# UsbHub.net
KiCad netlist of a schematic drawn in EasyEDA Pro
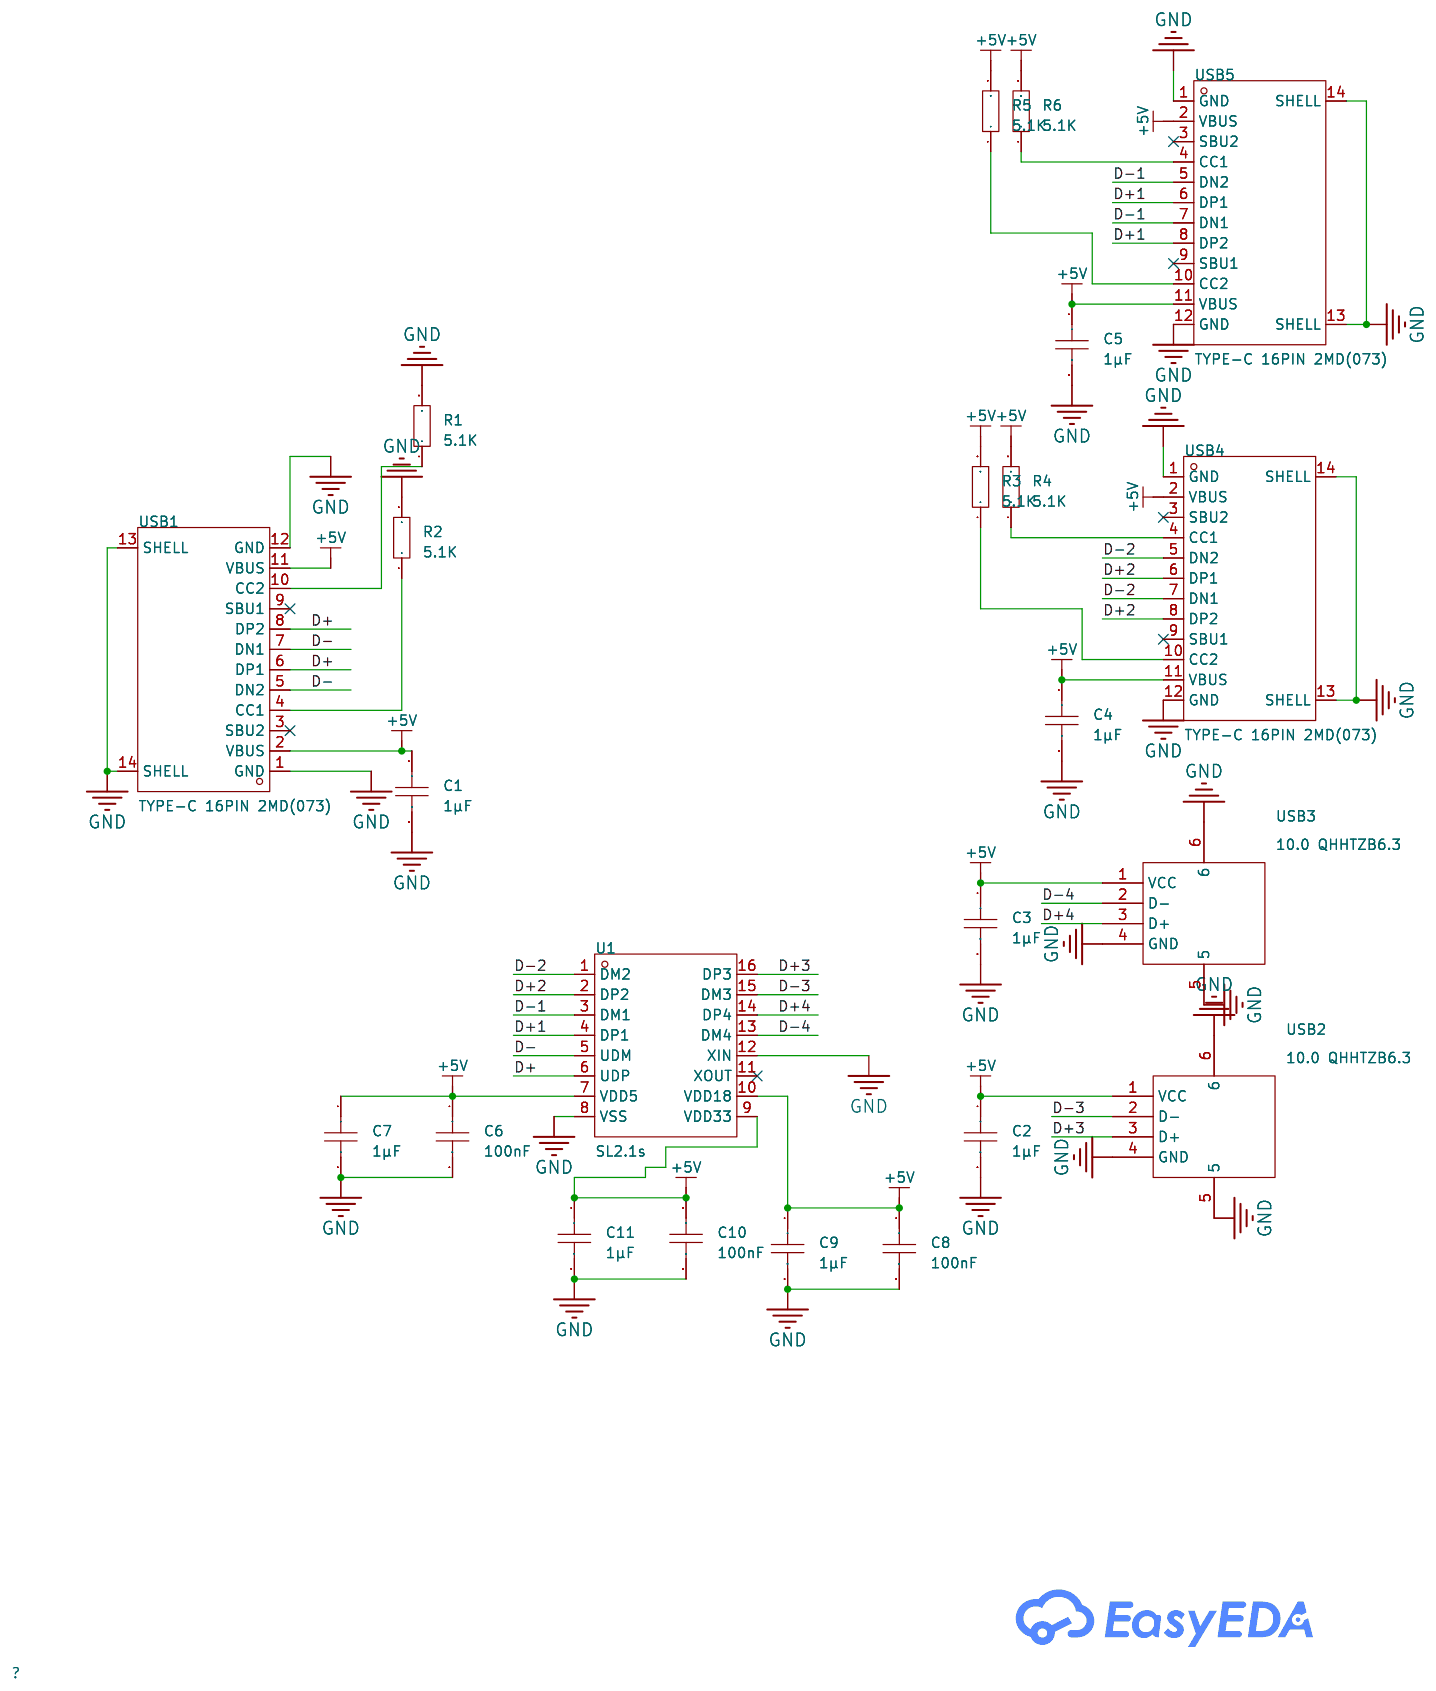
[diagram p0: schematic sheet]

(export (version "E")
  (design (tool "Eeschema 10.0.6"))
  (components
    (comp (ref "C1") (value "1µF") (footprint "easyedapro:C0603") (libsource (lib "easyedapro") (part "CAP")))
    (comp (ref "C2") (value "1µF") (footprint "easyedapro:C0603") (libsource (lib "easyedapro") (part "CAP")))
    (comp (ref "C3") (value "1µF") (footprint "easyedapro:C0603") (libsource (lib "easyedapro") (part "CAP")))
    (comp (ref "C4") (value "1µF") (footprint "easyedapro:C0603") (libsource (lib "easyedapro") (part "CAP")))
    (comp (ref "C5") (value "1µF") (footprint "easyedapro:C0603") (libsource (lib "easyedapro") (part "CAP")))
    (comp (ref "C6")
      (value "100nF")
      (footprint "easyedapro:C0603")
      (libsource (lib "easyedapro") (part "CAP"))
    )
    (comp (ref "C7") (value "1µF") (footprint "easyedapro:C0603") (libsource (lib "easyedapro") (part "CAP")))
    (comp (ref "C8")
      (value "100nF")
      (footprint "easyedapro:C0603")
      (libsource (lib "easyedapro") (part "CAP"))
    )
    (comp (ref "C9") (value "1µF") (footprint "easyedapro:C0603") (libsource (lib "easyedapro") (part "CAP")))
    (comp (ref "C10")
      (value "100nF")
      (footprint "easyedapro:C0603")
      (libsource (lib "easyedapro") (part "CAP"))
    )
    (comp (ref "C11")
      (value "1µF")
      (footprint "easyedapro:C0603")
      (libsource (lib "easyedapro") (part "CAP"))
    )
    (comp (ref "R1")
      (value "5.1K")
      (footprint "easyedapro:R0603")
      (libsource (lib "easyedapro") (part "Res"))
    )
    (comp (ref "R2")
      (value "5.1K")
      (footprint "easyedapro:R0603")
      (libsource (lib "easyedapro") (part "Res"))
    )
    (comp (ref "R3")
      (value "5.1K")
      (footprint "easyedapro:R0603")
      (libsource (lib "easyedapro") (part "Res"))
    )
    (comp (ref "R4")
      (value "5.1K")
      (footprint "easyedapro:R0603")
      (libsource (lib "easyedapro") (part "Res"))
    )
    (comp (ref "R5")
      (value "5.1K")
      (footprint "easyedapro:R0603")
      (libsource (lib "easyedapro") (part "Res"))
    )
    (comp (ref "R6")
      (value "5.1K")
      (footprint "easyedapro:R0603")
      (libsource (lib "easyedapro") (part "Res"))
    )
    (comp (ref "U1")
      (value "SL2.1s")
      (footprint "easyedapro:SSOP-16_L4.6-W2.6-P0.53-LS4.0-BL")
      (fields (field (name "Manufacturer") "CoreChips(和芯润德)"))
      (libsource (lib "easyedapro") (part "SL2.1S"))
    )
    (comp (ref "USB1")
      (value "TYPE-C 16PIN 2MD(073)")
      (footprint "easyedapro:USB-C-SMD_TYPE-C-6PIN-2MD-073")
      (fields (field (name "Manufacturer") "SHOU HAN(首韩)"))
      (libsource (lib "easyedapro") (part "TYPE-C 16PIN 2MD(073)"))
    )
    (comp (ref "USB2")
      (value "10.0 QHHTZB6.3")
      (footprint "easyedapro:USB-A-TH_10.0QHHTZB6.3")
      (fields (field (name "Manufacturer") "SHOU HAN(首韩)"))
      (libsource (lib "easyedapro") (part "10.0 QHHTZB6.3"))
    )
    (comp (ref "USB3")
      (value "10.0 QHHTZB6.3")
      (footprint "easyedapro:USB-A-TH_10.0QHHTZB6.3")
      (fields (field (name "Manufacturer") "SHOU HAN(首韩)"))
      (libsource (lib "easyedapro") (part "10.0 QHHTZB6.3"))
    )
    (comp (ref "USB4")
      (value "TYPE-C 16PIN 2MD(073)")
      (footprint "easyedapro:USB-C-SMD_TYPE-C-6PIN-2MD-073")
      (fields (field (name "Manufacturer") "SHOU HAN(首韩)"))
      (libsource (lib "easyedapro") (part "TYPE-C 16PIN 2MD(073)"))
    )
    (comp (ref "USB5")
      (value "TYPE-C 16PIN 2MD(073)")
      (footprint "easyedapro:USB-C-SMD_TYPE-C-6PIN-2MD-073")
      (fields (field (name "Manufacturer") "SHOU HAN(首韩)"))
      (libsource (lib "easyedapro") (part "TYPE-C 16PIN 2MD(073)"))
    )
  )
  (nets
    (net (code "1") (name "+5V") (class "Default")
      (node (ref "C1") (pin "1") (pinfunction "1_1") (pintype "input"))
      (node (ref "C10") (pin "1") (pinfunction "1_1") (pintype "input"))
      (node (ref "C11") (pin "1") (pinfunction "1_1") (pintype "input"))
      (node (ref "C2") (pin "1") (pinfunction "1_1") (pintype "input"))
      (node (ref "C3") (pin "1") (pinfunction "1_1") (pintype "input"))
      (node (ref "C4") (pin "1") (pinfunction "1_1") (pintype "input"))
      (node (ref "C5") (pin "1") (pinfunction "1_1") (pintype "input"))
      (node (ref "C6") (pin "1") (pinfunction "1_1") (pintype "input"))
      (node (ref "C7") (pin "1") (pinfunction "1_1") (pintype "input"))
      (node (ref "C8") (pin "1") (pinfunction "1_1") (pintype "input"))
      (node (ref "C9") (pin "1") (pinfunction "1_1") (pintype "input"))
      (node (ref "R3") (pin "2") (pinfunction "2_2") (pintype "input"))
      (node (ref "R4") (pin "2") (pinfunction "2_2") (pintype "input"))
      (node (ref "R5") (pin "2") (pinfunction "2_2") (pintype "input"))
      (node (ref "R6") (pin "2") (pinfunction "2_2") (pintype "input"))
      (node (ref "U1") (pin "10") (pinfunction "VDD18_10") (pintype "unspecified"))
      (node (ref "U1") (pin "7") (pinfunction "VDD5_7") (pintype "unspecified"))
      (node (ref "U1") (pin "9") (pinfunction "VDD33_9") (pintype "unspecified"))
      (node (ref "USB1") (pin "11") (pinfunction "VBUS_11") (pintype "unspecified"))
      (node (ref "USB1") (pin "2") (pinfunction "VBUS_2") (pintype "unspecified"))
      (node (ref "USB2") (pin "1") (pinfunction "VCC_1") (pintype "unspecified"))
      (node (ref "USB3") (pin "1") (pinfunction "VCC_1") (pintype "unspecified"))
      (node (ref "USB4") (pin "11") (pinfunction "VBUS_11") (pintype "unspecified"))
      (node (ref "USB4") (pin "2") (pinfunction "VBUS_2") (pintype "unspecified"))
      (node (ref "USB5") (pin "11") (pinfunction "VBUS_11") (pintype "unspecified"))
      (node (ref "USB5") (pin "2") (pinfunction "VBUS_2") (pintype "unspecified"))
    )
    (net (code "2") (name "/D+") (class "Default")
      (node (ref "U1") (pin "6") (pinfunction "UDP_6") (pintype "unspecified"))
      (node (ref "USB1") (pin "6") (pinfunction "DP1_6") (pintype "unspecified"))
      (node (ref "USB1") (pin "8") (pinfunction "DP2_8") (pintype "unspecified"))
    )
    (net (code "3") (name "/D+1") (class "Default")
      (node (ref "U1") (pin "4") (pinfunction "DP1_4") (pintype "unspecified"))
      (node (ref "USB5") (pin "6") (pinfunction "DP1_6") (pintype "unspecified"))
      (node (ref "USB5") (pin "8") (pinfunction "DP2_8") (pintype "unspecified"))
    )
    (net (code "4") (name "/D+2") (class "Default")
      (node (ref "U1") (pin "2") (pinfunction "DP2_2") (pintype "unspecified"))
      (node (ref "USB4") (pin "6") (pinfunction "DP1_6") (pintype "unspecified"))
      (node (ref "USB4") (pin "8") (pinfunction "DP2_8") (pintype "unspecified"))
    )
    (net (code "5") (name "/D+3") (class "Default")
      (node (ref "U1") (pin "16") (pinfunction "DP3_16") (pintype "unspecified"))
      (node (ref "USB2") (pin "3") (pinfunction "D+_3") (pintype "unspecified"))
    )
    (net (code "6") (name "/D+4") (class "Default")
      (node (ref "U1") (pin "14") (pinfunction "DP4_14") (pintype "unspecified"))
      (node (ref "USB3") (pin "3") (pinfunction "D+_3") (pintype "unspecified"))
    )
    (net (code "7") (name "/D-") (class "Default")
      (node (ref "U1") (pin "5") (pinfunction "UDM_5") (pintype "unspecified"))
      (node (ref "USB1") (pin "5") (pinfunction "DN2_5") (pintype "unspecified"))
      (node (ref "USB1") (pin "7") (pinfunction "DN1_7") (pintype "unspecified"))
    )
    (net (code "8") (name "/D-1") (class "Default")
      (node (ref "U1") (pin "3") (pinfunction "DM1_3") (pintype "unspecified"))
      (node (ref "USB5") (pin "5") (pinfunction "DN2_5") (pintype "unspecified"))
      (node (ref "USB5") (pin "7") (pinfunction "DN1_7") (pintype "unspecified"))
    )
    (net (code "9") (name "/D-2") (class "Default")
      (node (ref "U1") (pin "1") (pinfunction "DM2_1") (pintype "unspecified"))
      (node (ref "USB4") (pin "5") (pinfunction "DN2_5") (pintype "unspecified"))
      (node (ref "USB4") (pin "7") (pinfunction "DN1_7") (pintype "unspecified"))
    )
    (net (code "10") (name "/D-3") (class "Default")
      (node (ref "U1") (pin "15") (pinfunction "DM3_15") (pintype "unspecified"))
      (node (ref "USB2") (pin "2") (pinfunction "D-_2") (pintype "unspecified"))
    )
    (net (code "11") (name "/D-4") (class "Default")
      (node (ref "U1") (pin "13") (pinfunction "DM4_13") (pintype "unspecified"))
      (node (ref "USB3") (pin "2") (pinfunction "D-_2") (pintype "unspecified"))
    )
    (net (code "12") (name "GND") (class "Default")
      (node (ref "C1") (pin "2") (pinfunction "2_2") (pintype "input"))
      (node (ref "C10") (pin "2") (pinfunction "2_2") (pintype "input"))
      (node (ref "C11") (pin "2") (pinfunction "2_2") (pintype "input"))
      (node (ref "C2") (pin "2") (pinfunction "2_2") (pintype "input"))
      (node (ref "C3") (pin "2") (pinfunction "2_2") (pintype "input"))
      (node (ref "C4") (pin "2") (pinfunction "2_2") (pintype "input"))
      (node (ref "C5") (pin "2") (pinfunction "2_2") (pintype "input"))
      (node (ref "C6") (pin "2") (pinfunction "2_2") (pintype "input"))
      (node (ref "C7") (pin "2") (pinfunction "2_2") (pintype "input"))
      (node (ref "C8") (pin "2") (pinfunction "2_2") (pintype "input"))
      (node (ref "C9") (pin "2") (pinfunction "2_2") (pintype "input"))
      (node (ref "R1") (pin "2") (pinfunction "2_2") (pintype "input"))
      (node (ref "R2") (pin "2") (pinfunction "2_2") (pintype "input"))
      (node (ref "U1") (pin "12") (pinfunction "XIN_12") (pintype "unspecified"))
      (node (ref "U1") (pin "8") (pinfunction "VSS_8") (pintype "unspecified"))
      (node (ref "USB1") (pin "1") (pinfunction "GND_1") (pintype "unspecified"))
      (node (ref "USB1") (pin "12") (pinfunction "GND_12") (pintype "unspecified"))
      (node (ref "USB1") (pin "13") (pinfunction "SHELL_13") (pintype "unspecified"))
      (node (ref "USB1") (pin "14") (pinfunction "SHELL_14") (pintype "unspecified"))
      (node (ref "USB2") (pin "4") (pinfunction "GND_4") (pintype "unspecified"))
      (node (ref "USB2") (pin "5") (pinfunction "5_5") (pintype "unspecified"))
      (node (ref "USB2") (pin "6") (pinfunction "6_6") (pintype "unspecified"))
      (node (ref "USB3") (pin "4") (pinfunction "GND_4") (pintype "unspecified"))
      (node (ref "USB3") (pin "5") (pinfunction "5_5") (pintype "unspecified"))
      (node (ref "USB3") (pin "6") (pinfunction "6_6") (pintype "unspecified"))
      (node (ref "USB4") (pin "1") (pinfunction "GND_1") (pintype "unspecified"))
      (node (ref "USB4") (pin "12") (pinfunction "GND_12") (pintype "unspecified"))
      (node (ref "USB4") (pin "13") (pinfunction "SHELL_13") (pintype "unspecified"))
      (node (ref "USB4") (pin "14") (pinfunction "SHELL_14") (pintype "unspecified"))
      (node (ref "USB5") (pin "1") (pinfunction "GND_1") (pintype "unspecified"))
      (node (ref "USB5") (pin "12") (pinfunction "GND_12") (pintype "unspecified"))
      (node (ref "USB5") (pin "13") (pinfunction "SHELL_13") (pintype "unspecified"))
      (node (ref "USB5") (pin "14") (pinfunction "SHELL_14") (pintype "unspecified"))
    )
    (net (code "13") (name "Net-(USB1-CC1)") (class "Default")
      (node (ref "R2") (pin "1") (pinfunction "1_1") (pintype "input"))
      (node (ref "USB1") (pin "4") (pinfunction "CC1_4") (pintype "unspecified"))
    )
    (net (code "14") (name "Net-(USB1-CC2)") (class "Default")
      (node (ref "R1") (pin "1") (pinfunction "1_1") (pintype "input"))
      (node (ref "USB1") (pin "10") (pinfunction "CC2_10") (pintype "unspecified"))
    )
    (net (code "15") (name "Net-(USB4-CC1)") (class "Default")
      (node (ref "R4") (pin "1") (pinfunction "1_1") (pintype "input"))
      (node (ref "USB4") (pin "4") (pinfunction "CC1_4") (pintype "unspecified"))
    )
    (net (code "16") (name "Net-(USB4-CC2)") (class "Default")
      (node (ref "R3") (pin "1") (pinfunction "1_1") (pintype "input"))
      (node (ref "USB4") (pin "10") (pinfunction "CC2_10") (pintype "unspecified"))
    )
    (net (code "17") (name "Net-(USB5-CC1)") (class "Default")
      (node (ref "R6") (pin "1") (pinfunction "1_1") (pintype "input"))
      (node (ref "USB5") (pin "4") (pinfunction "CC1_4") (pintype "unspecified"))
    )
    (net (code "18") (name "Net-(USB5-CC2)") (class "Default")
      (node (ref "R5") (pin "1") (pinfunction "1_1") (pintype "input"))
      (node (ref "USB5") (pin "10") (pinfunction "CC2_10") (pintype "unspecified"))
    )
    (net (code "19") (name "unconnected-(U1-XOUT-Pad11)") (class "Default")
      (node (ref "U1") (pin "11") (pinfunction "XOUT_11") (pintype "unspecified+no_connect"))
    )
    (net (code "20") (name "unconnected-(USB1-SBU1-Pad9)") (class "Default")
      (node (ref "USB1") (pin "9") (pinfunction "SBU1_9") (pintype "unspecified+no_connect"))
    )
    (net (code "21") (name "unconnected-(USB1-SBU2-Pad3)") (class "Default")
      (node (ref "USB1") (pin "3") (pinfunction "SBU2_3") (pintype "unspecified+no_connect"))
    )
    (net (code "22") (name "unconnected-(USB4-SBU1-Pad9)") (class "Default")
      (node (ref "USB4") (pin "9") (pinfunction "SBU1_9") (pintype "unspecified+no_connect"))
    )
    (net (code "23") (name "unconnected-(USB4-SBU2-Pad3)") (class "Default")
      (node (ref "USB4") (pin "3") (pinfunction "SBU2_3") (pintype "unspecified+no_connect"))
    )
    (net (code "24") (name "unconnected-(USB5-SBU1-Pad9)") (class "Default")
      (node (ref "USB5") (pin "9") (pinfunction "SBU1_9") (pintype "unspecified+no_connect"))
    )
    (net (code "25") (name "unconnected-(USB5-SBU2-Pad3)") (class "Default")
      (node (ref "USB5") (pin "3") (pinfunction "SBU2_3") (pintype "unspecified+no_connect"))
    )
  )
)
